# Top.net
KiCad netlist of a schematic drawn in Altium Designer
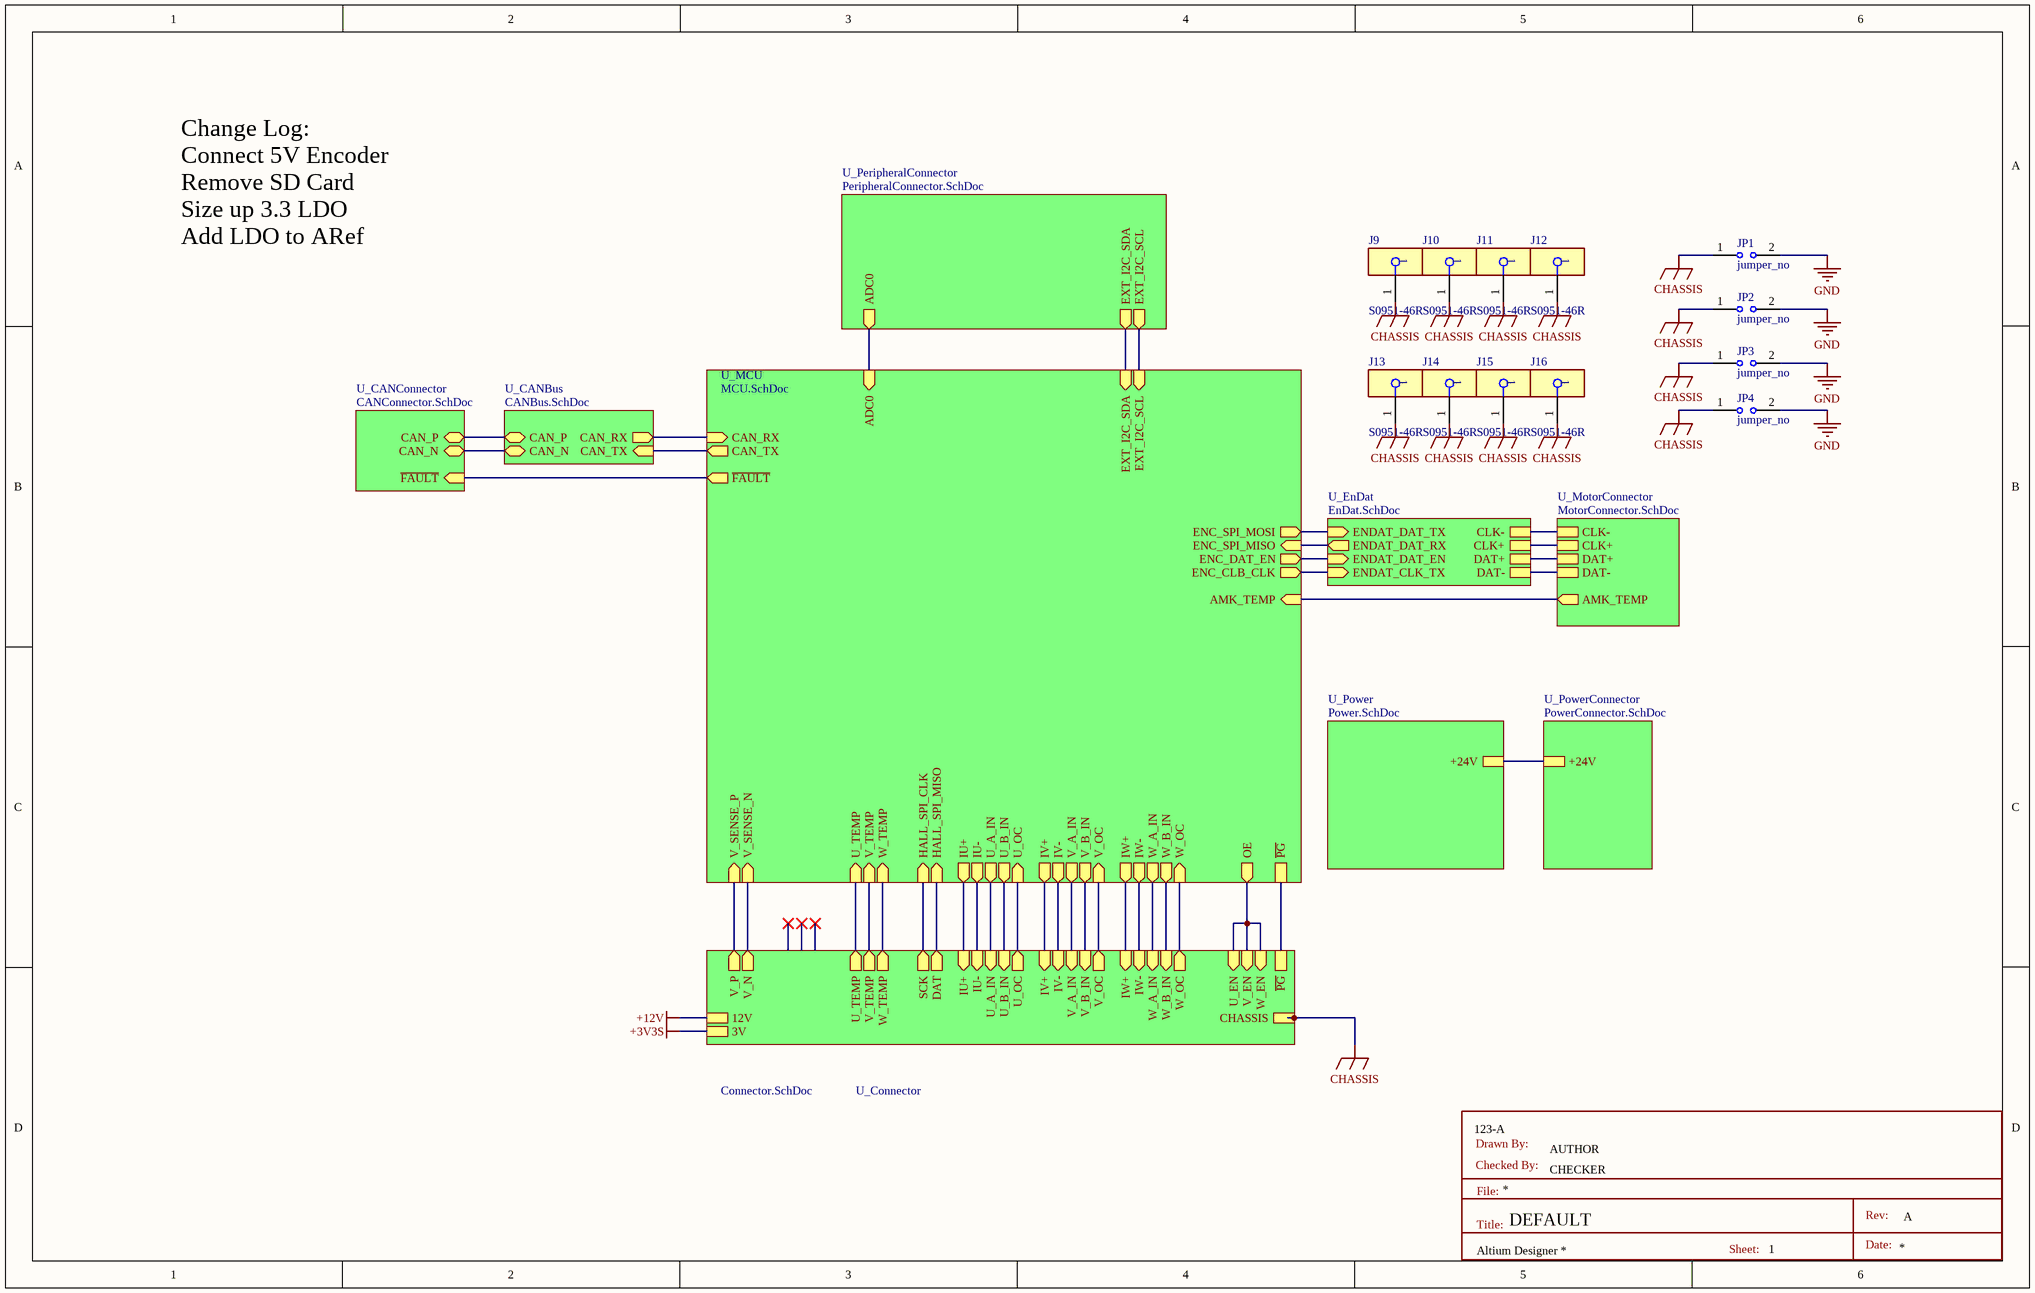
[diagram p0: Top.SchDoc]

(export (version "E")
  (design (tool "Eeschema 10.0.6"))
  (components
    (comp (ref "J9")
      (value "S0951-46R")
      (footprint "FP-S0951-46R-MFG")
      (description "RFI SHIELD CLIP MINI TIN SMD")
      (libsource (lib "Altium Content Vault") (part "98815daf2f2c152b0c43f5ab9800df6"))
    )
    (comp (ref "J10")
      (value "S0951-46R")
      (footprint "FP-S0951-46R-MFG")
      (description "RFI SHIELD CLIP MINI TIN SMD")
      (libsource (lib "Altium Content Vault") (part "98815daf2f2c152b0c43f5ab9800df6"))
    )
    (comp (ref "J11")
      (value "S0951-46R")
      (footprint "FP-S0951-46R-MFG")
      (description "RFI SHIELD CLIP MINI TIN SMD")
      (libsource (lib "Altium Content Vault") (part "98815daf2f2c152b0c43f5ab9800df6"))
    )
    (comp (ref "J12")
      (value "S0951-46R")
      (footprint "FP-S0951-46R-MFG")
      (description "RFI SHIELD CLIP MINI TIN SMD")
      (libsource (lib "Altium Content Vault") (part "98815daf2f2c152b0c43f5ab9800df6"))
    )
    (comp (ref "J13")
      (value "S0951-46R")
      (footprint "FP-S0951-46R-MFG")
      (description "RFI SHIELD CLIP MINI TIN SMD")
      (libsource (lib "Altium Content Vault") (part "98815daf2f2c152b0c43f5ab9800df6"))
    )
    (comp (ref "J14")
      (value "S0951-46R")
      (footprint "FP-S0951-46R-MFG")
      (description "RFI SHIELD CLIP MINI TIN SMD")
      (libsource (lib "Altium Content Vault") (part "98815daf2f2c152b0c43f5ab9800df6"))
    )
    (comp (ref "J15")
      (value "S0951-46R")
      (footprint "FP-S0951-46R-MFG")
      (description "RFI SHIELD CLIP MINI TIN SMD")
      (libsource (lib "Altium Content Vault") (part "98815daf2f2c152b0c43f5ab9800df6"))
    )
    (comp (ref "J16")
      (value "S0951-46R")
      (footprint "FP-S0951-46R-MFG")
      (description "RFI SHIELD CLIP MINI TIN SMD")
      (libsource (lib "Altium Content Vault") (part "98815daf2f2c152b0c43f5ab9800df6"))
    )
    (comp (ref "JP1")
      (value "jumper_no")
      (footprint "jumper_no")
      (libsource (lib "Schlib1") (part "jumper_no"))
    )
    (comp (ref "JP2")
      (value "jumper_no")
      (footprint "jumper_no")
      (libsource (lib "Schlib1") (part "jumper_no"))
    )
    (comp (ref "JP3")
      (value "jumper_no")
      (footprint "jumper_no")
      (libsource (lib "Schlib1") (part "jumper_no"))
    )
    (comp (ref "JP4")
      (value "jumper_no")
      (footprint "jumper_no")
      (libsource (lib "Schlib1") (part "jumper_no"))
    )
  )
  (nets
    (net (code "45") (name "CHASSIS") (class "Default")
      (node (ref "J10") (pin "1") (pinfunction "1_1") (pintype "passive"))
      (node (ref "J11") (pin "1") (pinfunction "1_1") (pintype "passive"))
      (node (ref "J12") (pin "1") (pinfunction "1_1") (pintype "passive"))
      (node (ref "J13") (pin "1") (pinfunction "1_1") (pintype "passive"))
      (node (ref "J14") (pin "1") (pinfunction "1_1") (pintype "passive"))
      (node (ref "J15") (pin "1") (pinfunction "1_1") (pintype "passive"))
      (node (ref "J16") (pin "1") (pinfunction "1_1") (pintype "passive"))
      (node (ref "J9") (pin "1") (pinfunction "1_1") (pintype "passive"))
      (node (ref "JP1") (pin "1") (pinfunction "1_1") (pintype "passive"))
      (node (ref "JP2") (pin "1") (pinfunction "1_1") (pintype "passive"))
      (node (ref "JP3") (pin "1") (pinfunction "1_1") (pintype "passive"))
      (node (ref "JP4") (pin "1") (pinfunction "1_1") (pintype "passive"))
    )
    (net (code "46") (name "GND") (class "Default")
      (node (ref "JP1") (pin "2") (pinfunction "2_2") (pintype "passive"))
      (node (ref "JP2") (pin "2") (pinfunction "2_2") (pintype "passive"))
      (node (ref "JP3") (pin "2") (pinfunction "2_2") (pintype "passive"))
      (node (ref "JP4") (pin "2") (pinfunction "2_2") (pintype "passive"))
    )
  )
)
